# SportsLight.net
KiCad netlist of a schematic drawn in Altium Designer
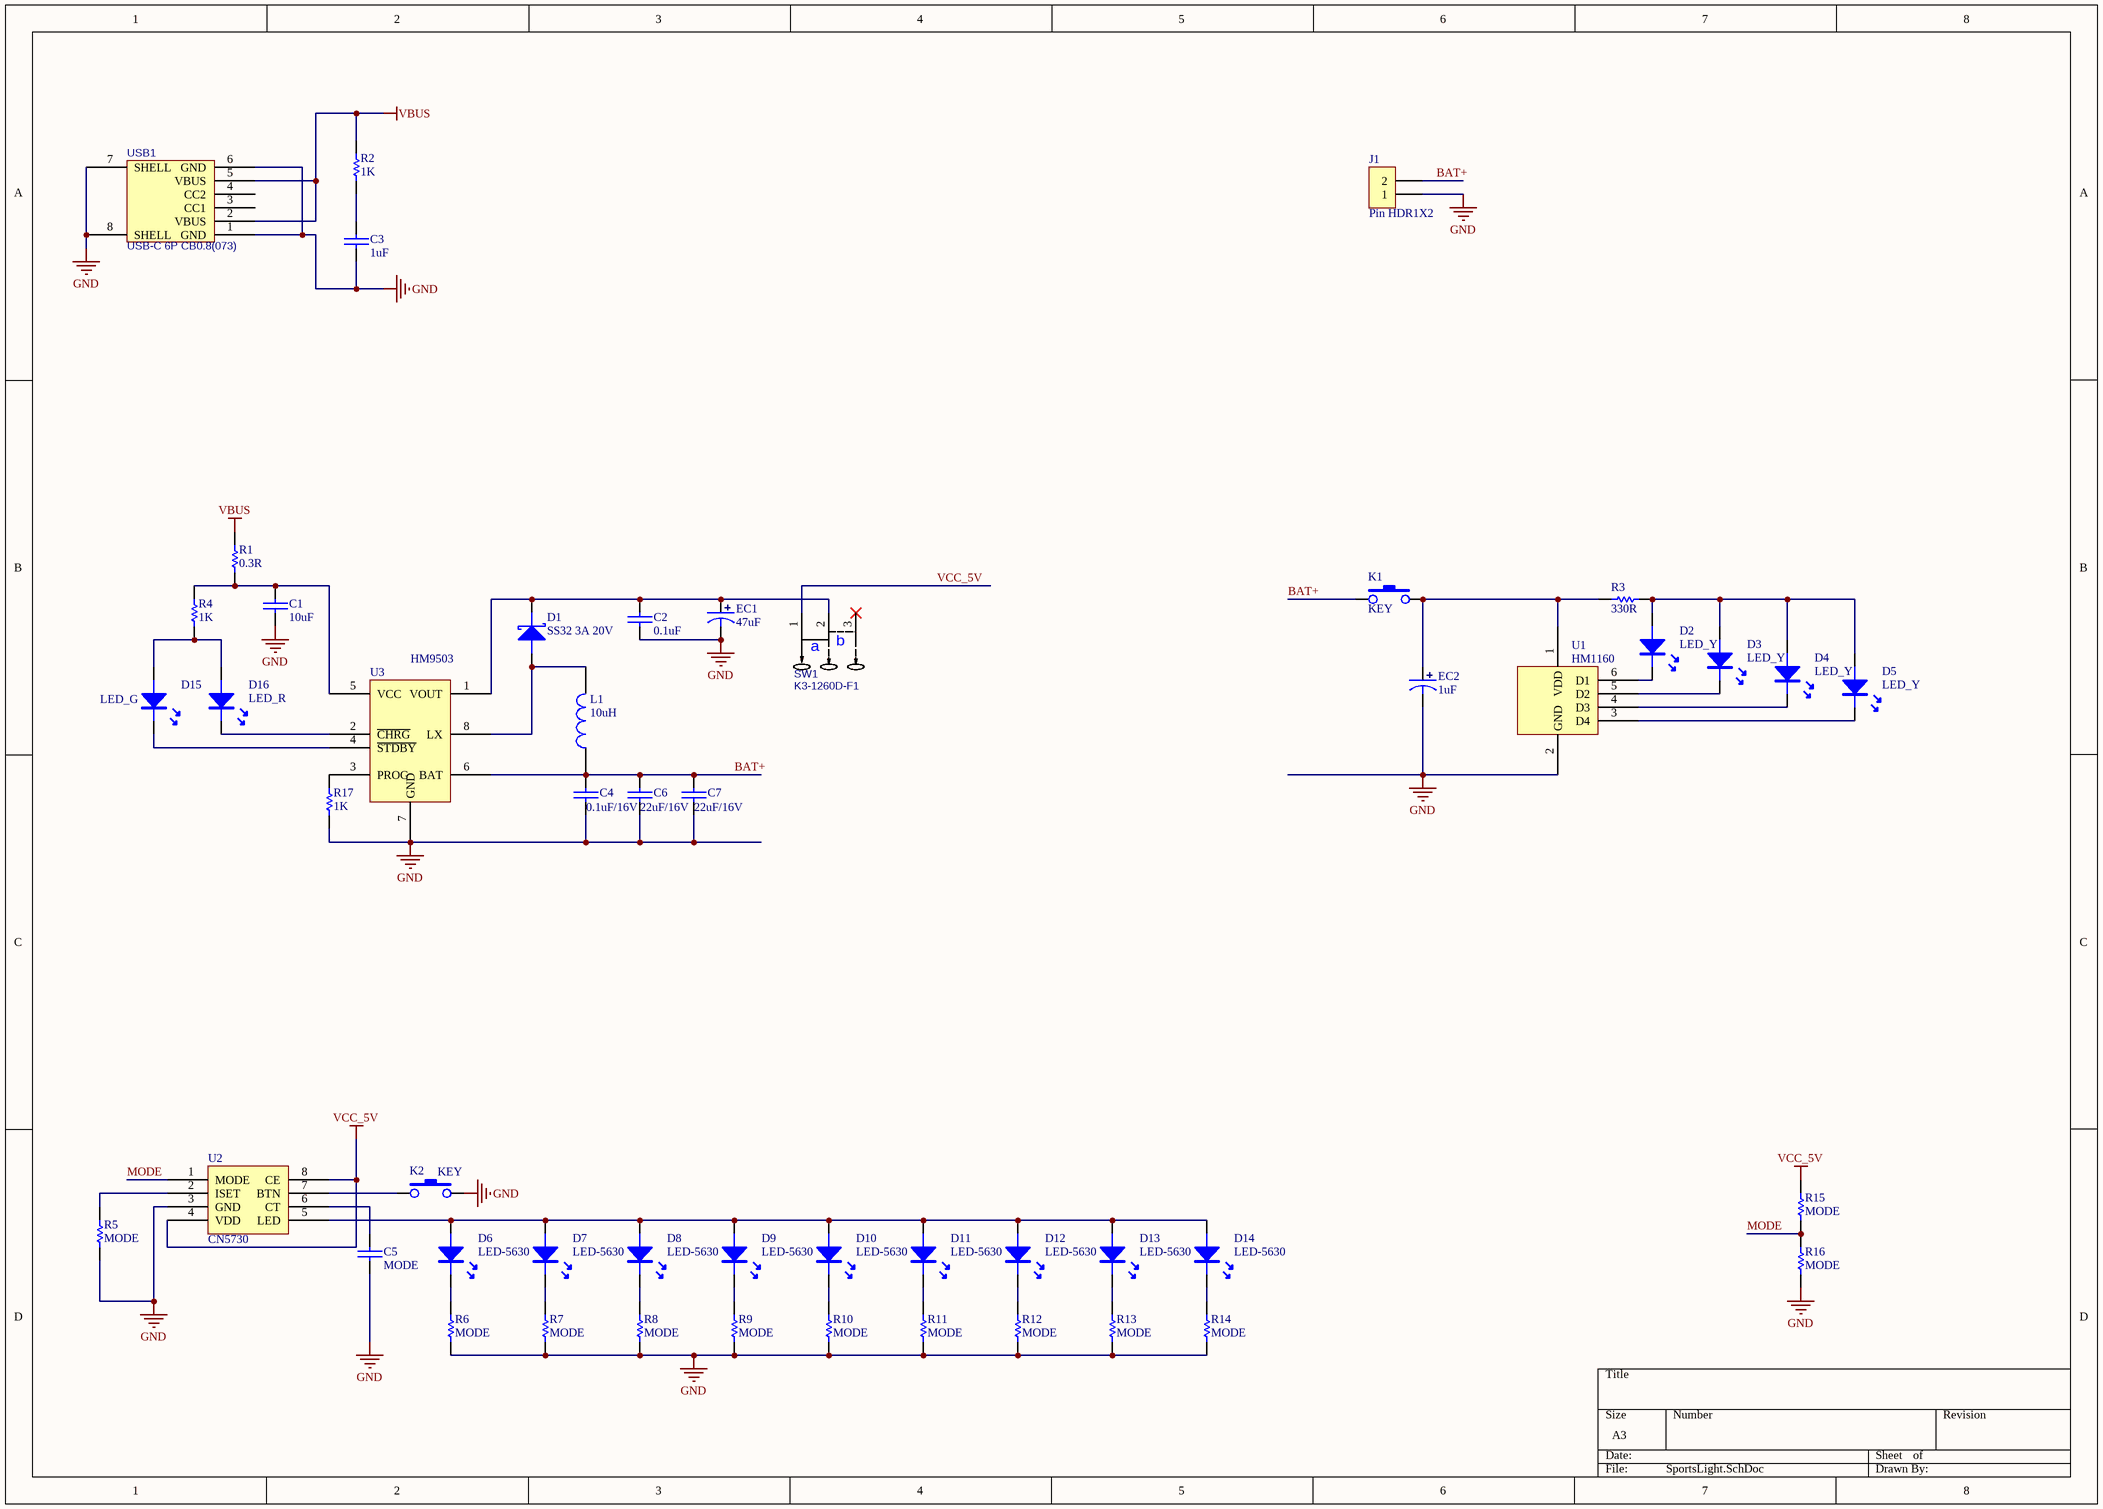
[diagram p0: SportsLight.SchDoc]

(export (version "E")
  (design (tool "Eeschema 10.0.6"))
  (components
    (comp (ref "C1")
      (value "10uF")
      (footprint "0603C")
      (description "无极性电容")
      (libsource (lib "电容") (part "CAP"))
    )
    (comp (ref "C2")
      (value "0.1uF")
      (footprint "0603C")
      (description "无极性电容")
      (libsource (lib "电容") (part "CAP"))
    )
    (comp (ref "C3")
      (value "1uF")
      (footprint "0603C")
      (description "无极性电容")
      (libsource (lib "电容") (part "CAP"))
    )
    (comp (ref "C4")
      (value "0.1uF/16V")
      (footprint "0603C")
      (description "无极性电容")
      (libsource (lib "电容") (part "CAP"))
    )
    (comp (ref "C5")
      (value "MODE")
      (footprint "0603C")
      (description "无极性电容")
      (libsource (lib "电容") (part "CAP"))
    )
    (comp (ref "C6")
      (value "22uF/16V")
      (footprint "0603C")
      (description "无极性电容")
      (libsource (lib "电容") (part "CAP"))
    )
    (comp (ref "C7")
      (value "22uF/16V")
      (footprint "0603C")
      (description "无极性电容")
      (libsource (lib "电容") (part "CAP"))
    )
    (comp (ref "D1")
      (value "SS32 3A 20V")
      (footprint "SMA/DO-214AC")
      (description "肖特基二极管")
      (libsource (lib "二极管") (part "DIODE SCHOTTKY"))
    )
    (comp (ref "D2") (value "LED_Y") (footprint "LED-0602-RD") (libsource (lib "LED") (part "LED")))
    (comp (ref "D3") (value "LED_Y") (footprint "LED-0602-RD") (libsource (lib "LED") (part "LED")))
    (comp (ref "D4") (value "LED_Y") (footprint "LED-0602-RD") (libsource (lib "LED") (part "LED")))
    (comp (ref "D5") (value "LED_Y") (footprint "LED-0602-RD") (libsource (lib "LED") (part "LED")))
    (comp (ref "D6") (value "LED-5630") (footprint "LED-5630W") (libsource (lib "LED") (part "LED-5630")))
    (comp (ref "D7") (value "LED-5630") (footprint "LED-5630W") (libsource (lib "LED") (part "LED-5630")))
    (comp (ref "D8") (value "LED-5630") (footprint "LED-5630W") (libsource (lib "LED") (part "LED-5630")))
    (comp (ref "D9") (value "LED-5630") (footprint "LED-5630W") (libsource (lib "LED") (part "LED-5630")))
    (comp (ref "D10") (value "LED-5630") (footprint "LED-5630W") (libsource (lib "LED") (part "LED-5630")))
    (comp (ref "D11") (value "LED-5630") (footprint "LED-5630W") (libsource (lib "LED") (part "LED-5630")))
    (comp (ref "D12") (value "LED-5630") (footprint "LED-5630W") (libsource (lib "LED") (part "LED-5630")))
    (comp (ref "D13") (value "LED-5630") (footprint "LED-5630W") (libsource (lib "LED") (part "LED-5630")))
    (comp (ref "D14") (value "LED-5630") (footprint "LED-5630W") (libsource (lib "LED") (part "LED-5630")))
    (comp (ref "D15") (value "LED_G") (footprint "LED-0602-RD") (libsource (lib "LED") (part "LED")))
    (comp (ref "D16") (value "LED_R") (footprint "LED-0602-RD") (libsource (lib "LED") (part "LED")))
    (comp (ref "EC1")
      (value "47uF")
      (footprint "SMD-EC4.0X4.3X5.4")
      (description "贴片电解电容")
      (libsource (lib "电容") (part "SMD_ECAP"))
    )
    (comp (ref "EC2")
      (value "1uF")
      (footprint "SMD-EC4.0X4.3X5.4")
      (description "贴片电解电容")
      (libsource (lib "电容") (part "SMD_ECAP"))
    )
    (comp (ref "J1")
      (value "Pin HDR1X2")
      (footprint "Pin HDR1X2/2.54mm-S")
      (libsource (lib "排针") (part "Pin HDR1X2"))
    )
    (comp (ref "K1") (value "KEY") (footprint "SMD-3.5x7.8x2.5_C") (libsource (lib "轻触开关") (part "KEY")))
    (comp (ref "K2") (value "KEY") (footprint "SMD-3.5x7.8x2.5_C") (libsource (lib "轻触开关") (part "KEY")))
    (comp (ref "L1")
      (value "10uH")
      (footprint "0630L")
      (description "INDUCTOR")
      (libsource (lib "电感") (part "INDUCTOR"))
    )
    (comp (ref "R1") (value "0.3R") (footprint "0603R") (libsource (lib "电阻") (part "RES")))
    (comp (ref "R2") (value "1K") (footprint "0603R") (libsource (lib "电阻") (part "RES")))
    (comp (ref "R3") (value "330R") (footprint "0603R") (libsource (lib "电阻") (part "RES")))
    (comp (ref "R4") (value "1K") (footprint "0603R") (libsource (lib "电阻") (part "RES")))
    (comp (ref "R5") (value "MODE") (footprint "0603R") (libsource (lib "电阻") (part "RES")))
    (comp (ref "R6") (value "MODE") (footprint "0603R") (libsource (lib "电阻") (part "RES")))
    (comp (ref "R7") (value "MODE") (footprint "0603R") (libsource (lib "电阻") (part "RES")))
    (comp (ref "R8") (value "MODE") (footprint "0603R") (libsource (lib "电阻") (part "RES")))
    (comp (ref "R9") (value "MODE") (footprint "0603R") (libsource (lib "电阻") (part "RES")))
    (comp (ref "R10") (value "MODE") (footprint "0603R") (libsource (lib "电阻") (part "RES")))
    (comp (ref "R11") (value "MODE") (footprint "0603R") (libsource (lib "电阻") (part "RES")))
    (comp (ref "R12") (value "MODE") (footprint "0603R") (libsource (lib "电阻") (part "RES")))
    (comp (ref "R13") (value "MODE") (footprint "0603R") (libsource (lib "电阻") (part "RES")))
    (comp (ref "R14") (value "MODE") (footprint "0603R") (libsource (lib "电阻") (part "RES")))
    (comp (ref "R15") (value "MODE") (footprint "0603R") (libsource (lib "电阻") (part "RES")))
    (comp (ref "R16") (value "MODE") (footprint "0603R") (libsource (lib "电阻") (part "RES")))
    (comp (ref "R17") (value "1K") (footprint "0603R") (libsource (lib "电阻") (part "RES")))
    (comp (ref "SW1")
      (value "K3-1260D-F1")
      (footprint "SK-3260D-01-L3")
      (fields (field (name "BOM_SUPPLIER PART") "C223843") (field (name "CONTRIBUTOR") "LCSC"))
      (libsource (lib "电源开关") (part "K3-1260D-F1"))
    )
    (comp (ref "U1")
      (value "HM1160")
      (footprint "SOT23-6")
      (description "单节锂电池电量指示芯片")
      (libsource (lib "电源芯片") (part "HM1160"))
    )
    (comp (ref "U2")
      (value "CN5730")
      (footprint "ESOP8")
      (description "LED集成驱动电路")
      (libsource (lib "未分类IC") (part "CN5730"))
    )
    (comp (ref "U3")
      (value "HM9503")
      (footprint "ESOP8")
      (description "1A锂电池充电和5V/1A升压控制芯片")
      (libsource (lib "电源芯片") (part "HM9503"))
    )
    (comp (ref "USB1")
      (value "USB-C 6P CB0.8(073)")
      (footprint "USB-C-SMD_TYPE-C-6P-CB0.8-073")
      (fields
        (field (name "BOM_SUPPLIER PART") "C2858273")
        (field (name "BOM_MANUFACTURER PART") "TYPE-C 6P CB0.8(073)")
        (field (name "CONTRIBUTOR") "LCSC")
      )
      (libsource (lib "USB") (part "USB-C 6P CB0.8(073)"))
    )
  )
  (nets
    (net (code "1") (name "/BAT+") (class "Default")
      (node (ref "C4") (pin "2") (pinfunction "2_2") (pintype "passive"))
      (node (ref "C6") (pin "2") (pinfunction "2_2") (pintype "passive"))
      (node (ref "C7") (pin "2") (pinfunction "2_2") (pintype "passive"))
      (node (ref "J1") (pin "2") (pinfunction "2_2") (pintype "passive"))
      (node (ref "K1") (pin "1") (pinfunction "1_1") (pintype "passive"))
      (node (ref "L1") (pin "1") (pinfunction "1_1") (pintype "passive"))
      (node (ref "U3") (pin "6") (pinfunction "BAT_6") (pintype "passive"))
    )
    (net (code "2") (name "/MODE") (class "Default")
      (node (ref "R15") (pin "2") (pinfunction "2_2") (pintype "passive"))
      (node (ref "R16") (pin "2") (pinfunction "2_2") (pintype "passive"))
      (node (ref "U2") (pin "1") (pinfunction "MODE_1") (pintype "passive"))
    )
    (net (code "3") (name "GND") (class "Default")
      (node (ref "C1") (pin "1") (pinfunction "1_1") (pintype "passive"))
      (node (ref "C2") (pin "1") (pinfunction "1_1") (pintype "passive"))
      (node (ref "C3") (pin "1") (pinfunction "1_1") (pintype "passive"))
      (node (ref "C4") (pin "1") (pinfunction "1_1") (pintype "passive"))
      (node (ref "C5") (pin "2") (pinfunction "2_2") (pintype "passive"))
      (node (ref "C6") (pin "1") (pinfunction "1_1") (pintype "passive"))
      (node (ref "C7") (pin "1") (pinfunction "1_1") (pintype "passive"))
      (node (ref "EC1") (pin "2") (pinfunction "2_2") (pintype "passive"))
      (node (ref "EC2") (pin "2") (pinfunction "2_2") (pintype "passive"))
      (node (ref "J1") (pin "1") (pinfunction "1_1") (pintype "passive"))
      (node (ref "K2") (pin "3") (pinfunction "3_3") (pintype "passive"))
      (node (ref "R10") (pin "1") (pinfunction "1_1") (pintype "passive"))
      (node (ref "R11") (pin "1") (pinfunction "1_1") (pintype "passive"))
      (node (ref "R12") (pin "1") (pinfunction "1_1") (pintype "passive"))
      (node (ref "R13") (pin "1") (pinfunction "1_1") (pintype "passive"))
      (node (ref "R14") (pin "1") (pinfunction "1_1") (pintype "passive"))
      (node (ref "R16") (pin "1") (pinfunction "1_1") (pintype "passive"))
      (node (ref "R17") (pin "1") (pinfunction "1_1") (pintype "passive"))
      (node (ref "R5") (pin "1") (pinfunction "1_1") (pintype "passive"))
      (node (ref "R6") (pin "1") (pinfunction "1_1") (pintype "passive"))
      (node (ref "R7") (pin "1") (pinfunction "1_1") (pintype "passive"))
      (node (ref "R8") (pin "1") (pinfunction "1_1") (pintype "passive"))
      (node (ref "R9") (pin "1") (pinfunction "1_1") (pintype "passive"))
      (node (ref "U1") (pin "2") (pinfunction "GND_2") (pintype "passive"))
      (node (ref "U2") (pin "3") (pinfunction "GND_3") (pintype "passive"))
      (node (ref "U3") (pin "7") (pinfunction "GND_7") (pintype "passive"))
      (node (ref "USB1") (pin "1") (pinfunction "GND_1") (pintype "passive"))
      (node (ref "USB1") (pin "6") (pinfunction "GND_6") (pintype "passive"))
      (node (ref "USB1") (pin "7") (pinfunction "SHELL_7") (pintype "passive"))
      (node (ref "USB1") (pin "8") (pinfunction "SHELL_8") (pintype "passive"))
    )
    (net (code "4") (name "Net-(C3-Pad2)") (class "Default")
      (node (ref "C3") (pin "2") (pinfunction "2_2") (pintype "passive"))
      (node (ref "R2") (pin "1") (pinfunction "1_1") (pintype "passive"))
    )
    (net (code "5") (name "Net-(D2-PadA)") (class "Default")
      (node (ref "D2") (pin "A") (pinfunction "A_A") (pintype "passive"))
      (node (ref "D3") (pin "A") (pinfunction "A_A") (pintype "passive"))
      (node (ref "D4") (pin "A") (pinfunction "A_A") (pintype "passive"))
      (node (ref "D5") (pin "A") (pinfunction "A_A") (pintype "passive"))
      (node (ref "R3") (pin "1") (pinfunction "1_1") (pintype "passive"))
    )
    (net (code "6") (name "Net-(D6-PadK)") (class "Default")
      (node (ref "D6") (pin "K") (pinfunction "K_K") (pintype "passive"))
      (node (ref "R6") (pin "2") (pinfunction "2_2") (pintype "passive"))
    )
    (net (code "7") (name "Net-(D7-PadK)") (class "Default")
      (node (ref "D7") (pin "K") (pinfunction "K_K") (pintype "passive"))
      (node (ref "R7") (pin "2") (pinfunction "2_2") (pintype "passive"))
    )
    (net (code "8") (name "Net-(D8-PadK)") (class "Default")
      (node (ref "D8") (pin "K") (pinfunction "K_K") (pintype "passive"))
      (node (ref "R8") (pin "2") (pinfunction "2_2") (pintype "passive"))
    )
    (net (code "9") (name "Net-(D9-PadK)") (class "Default")
      (node (ref "D9") (pin "K") (pinfunction "K_K") (pintype "passive"))
      (node (ref "R9") (pin "2") (pinfunction "2_2") (pintype "passive"))
    )
    (net (code "10") (name "Net-(D10-PadK)") (class "Default")
      (node (ref "D10") (pin "K") (pinfunction "K_K") (pintype "passive"))
      (node (ref "R10") (pin "2") (pinfunction "2_2") (pintype "passive"))
    )
    (net (code "11") (name "Net-(D11-PadK)") (class "Default")
      (node (ref "D11") (pin "K") (pinfunction "K_K") (pintype "passive"))
      (node (ref "R11") (pin "2") (pinfunction "2_2") (pintype "passive"))
    )
    (net (code "12") (name "Net-(D12-PadK)") (class "Default")
      (node (ref "D12") (pin "K") (pinfunction "K_K") (pintype "passive"))
      (node (ref "R12") (pin "2") (pinfunction "2_2") (pintype "passive"))
    )
    (net (code "13") (name "Net-(D13-PadK)") (class "Default")
      (node (ref "D13") (pin "K") (pinfunction "K_K") (pintype "passive"))
      (node (ref "R13") (pin "2") (pinfunction "2_2") (pintype "passive"))
    )
    (net (code "14") (name "Net-(D14-PadK)") (class "Default")
      (node (ref "D14") (pin "K") (pinfunction "K_K") (pintype "passive"))
      (node (ref "R14") (pin "2") (pinfunction "2_2") (pintype "passive"))
    )
    (net (code "15") (name "Net-(D15-PadA)") (class "Default")
      (node (ref "D15") (pin "A") (pinfunction "A_A") (pintype "passive"))
      (node (ref "D16") (pin "A") (pinfunction "A_A") (pintype "passive"))
      (node (ref "R4") (pin "1") (pinfunction "1_1") (pintype "passive"))
    )
    (net (code "16") (name "Net-(U1-D1)") (class "Default")
      (node (ref "D2") (pin "K") (pinfunction "K_K") (pintype "passive"))
      (node (ref "U1") (pin "6") (pinfunction "D1_6") (pintype "passive"))
    )
    (net (code "17") (name "Net-(U1-D2)") (class "Default")
      (node (ref "D3") (pin "K") (pinfunction "K_K") (pintype "passive"))
      (node (ref "U1") (pin "5") (pinfunction "D2_5") (pintype "passive"))
    )
    (net (code "18") (name "Net-(U1-D3)") (class "Default")
      (node (ref "D4") (pin "K") (pinfunction "K_K") (pintype "passive"))
      (node (ref "U1") (pin "4") (pinfunction "D3_4") (pintype "passive"))
    )
    (net (code "19") (name "Net-(U1-D4)") (class "Default")
      (node (ref "D5") (pin "K") (pinfunction "K_K") (pintype "passive"))
      (node (ref "U1") (pin "3") (pinfunction "D4_3") (pintype "passive"))
    )
    (net (code "20") (name "Net-(U1-VDD)") (class "Default")
      (node (ref "EC2") (pin "1") (pinfunction "1_1") (pintype "passive"))
      (node (ref "K1") (pin "3") (pinfunction "3_3") (pintype "passive"))
      (node (ref "R3") (pin "2") (pinfunction "2_2") (pintype "passive"))
      (node (ref "U1") (pin "1") (pinfunction "VDD_1") (pintype "passive"))
    )
    (net (code "21") (name "Net-(U2-BTN)") (class "Default")
      (node (ref "K2") (pin "1") (pinfunction "1_1") (pintype "passive"))
      (node (ref "U2") (pin "7") (pinfunction "BTN_7") (pintype "passive"))
    )
    (net (code "22") (name "Net-(U2-CT)") (class "Default")
      (node (ref "C5") (pin "1") (pinfunction "1_1") (pintype "passive"))
      (node (ref "U2") (pin "6") (pinfunction "CT_6") (pintype "passive"))
    )
    (net (code "23") (name "Net-(U2-ISET)") (class "Default")
      (node (ref "R5") (pin "2") (pinfunction "2_2") (pintype "passive"))
      (node (ref "U2") (pin "2") (pinfunction "ISET_2") (pintype "passive"))
    )
    (net (code "24") (name "Net-(U2-LED)") (class "Default")
      (node (ref "D10") (pin "A") (pinfunction "A_A") (pintype "passive"))
      (node (ref "D11") (pin "A") (pinfunction "A_A") (pintype "passive"))
      (node (ref "D12") (pin "A") (pinfunction "A_A") (pintype "passive"))
      (node (ref "D13") (pin "A") (pinfunction "A_A") (pintype "passive"))
      (node (ref "D14") (pin "A") (pinfunction "A_A") (pintype "passive"))
      (node (ref "D6") (pin "A") (pinfunction "A_A") (pintype "passive"))
      (node (ref "D7") (pin "A") (pinfunction "A_A") (pintype "passive"))
      (node (ref "D8") (pin "A") (pinfunction "A_A") (pintype "passive"))
      (node (ref "D9") (pin "A") (pinfunction "A_A") (pintype "passive"))
      (node (ref "U2") (pin "5") (pinfunction "LED_5") (pintype "passive"))
    )
    (net (code "25") (name "Net-(U3-LX)") (class "Default")
      (node (ref "D1") (pin "A") (pinfunction "A_A") (pintype "passive"))
      (node (ref "L1") (pin "2") (pinfunction "2_2") (pintype "passive"))
      (node (ref "U3") (pin "8") (pinfunction "LX_8") (pintype "passive"))
    )
    (net (code "26") (name "Net-(U3-PROG)") (class "Default")
      (node (ref "R17") (pin "2") (pinfunction "2_2") (pintype "passive"))
      (node (ref "U3") (pin "3") (pinfunction "PROG_3") (pintype "passive"))
    )
    (net (code "27") (name "Net-(U3-VCC)") (class "Default")
      (node (ref "C1") (pin "2") (pinfunction "2_2") (pintype "passive"))
      (node (ref "R1") (pin "1") (pinfunction "1_1") (pintype "passive"))
      (node (ref "R4") (pin "2") (pinfunction "2_2") (pintype "passive"))
      (node (ref "U3") (pin "5") (pinfunction "VCC_5") (pintype "passive"))
    )
    (net (code "28") (name "Net-(U3-VOUT)") (class "Default")
      (node (ref "C2") (pin "2") (pinfunction "2_2") (pintype "passive"))
      (node (ref "D1") (pin "K") (pinfunction "K_K") (pintype "passive"))
      (node (ref "EC1") (pin "1") (pinfunction "1_1") (pintype "passive"))
      (node (ref "SW1") (pin "2") (pinfunction "2_2") (pintype "passive"))
      (node (ref "U3") (pin "1") (pinfunction "VOUT_1") (pintype "passive"))
    )
    (net (code "29") (name "Net-(U3-~{CHRG})") (class "Default")
      (node (ref "D16") (pin "K") (pinfunction "K_K") (pintype "passive"))
      (node (ref "U3") (pin "2") (pinfunction "~{CHRG}_2") (pintype "passive"))
    )
    (net (code "30") (name "Net-(U3-~{STDBY})") (class "Default")
      (node (ref "D15") (pin "K") (pinfunction "K_K") (pintype "passive"))
      (node (ref "U3") (pin "4") (pinfunction "~{STDBY}_4") (pintype "passive"))
    )
    (net (code "31") (name "VBUS") (class "Default")
      (node (ref "R1") (pin "2") (pinfunction "2_2") (pintype "passive"))
      (node (ref "R2") (pin "2") (pinfunction "2_2") (pintype "passive"))
      (node (ref "USB1") (pin "2") (pinfunction "VBUS_2") (pintype "passive"))
      (node (ref "USB1") (pin "5") (pinfunction "VBUS_5") (pintype "passive"))
    )
    (net (code "32") (name "VCC_5V") (class "Default")
      (node (ref "R15") (pin "1") (pinfunction "1_1") (pintype "passive"))
      (node (ref "SW1") (pin "1") (pinfunction "1_1") (pintype "passive"))
      (node (ref "U2") (pin "4") (pinfunction "VDD_4") (pintype "passive"))
      (node (ref "U2") (pin "8") (pinfunction "CE_8") (pintype "passive"))
    )
    (net (code "33") (name "unconnected-(SW1-Pad3)") (class "Default")
      (node (ref "SW1") (pin "3") (pinfunction "3_3") (pintype "passive+no_connect"))
    )
    (net (code "34") (name "unconnected-(USB1-CC1-Pad3)") (class "Default")
      (node (ref "USB1") (pin "3") (pinfunction "CC1_3") (pintype "passive"))
    )
    (net (code "35") (name "unconnected-(USB1-CC2-Pad4)") (class "Default")
      (node (ref "USB1") (pin "4") (pinfunction "CC2_4") (pintype "passive"))
    )
  )
)
